# KNXTransceiverBoard_Aufsteck_V1.net
KiCad netlist of a schematic drawn in EAGLE
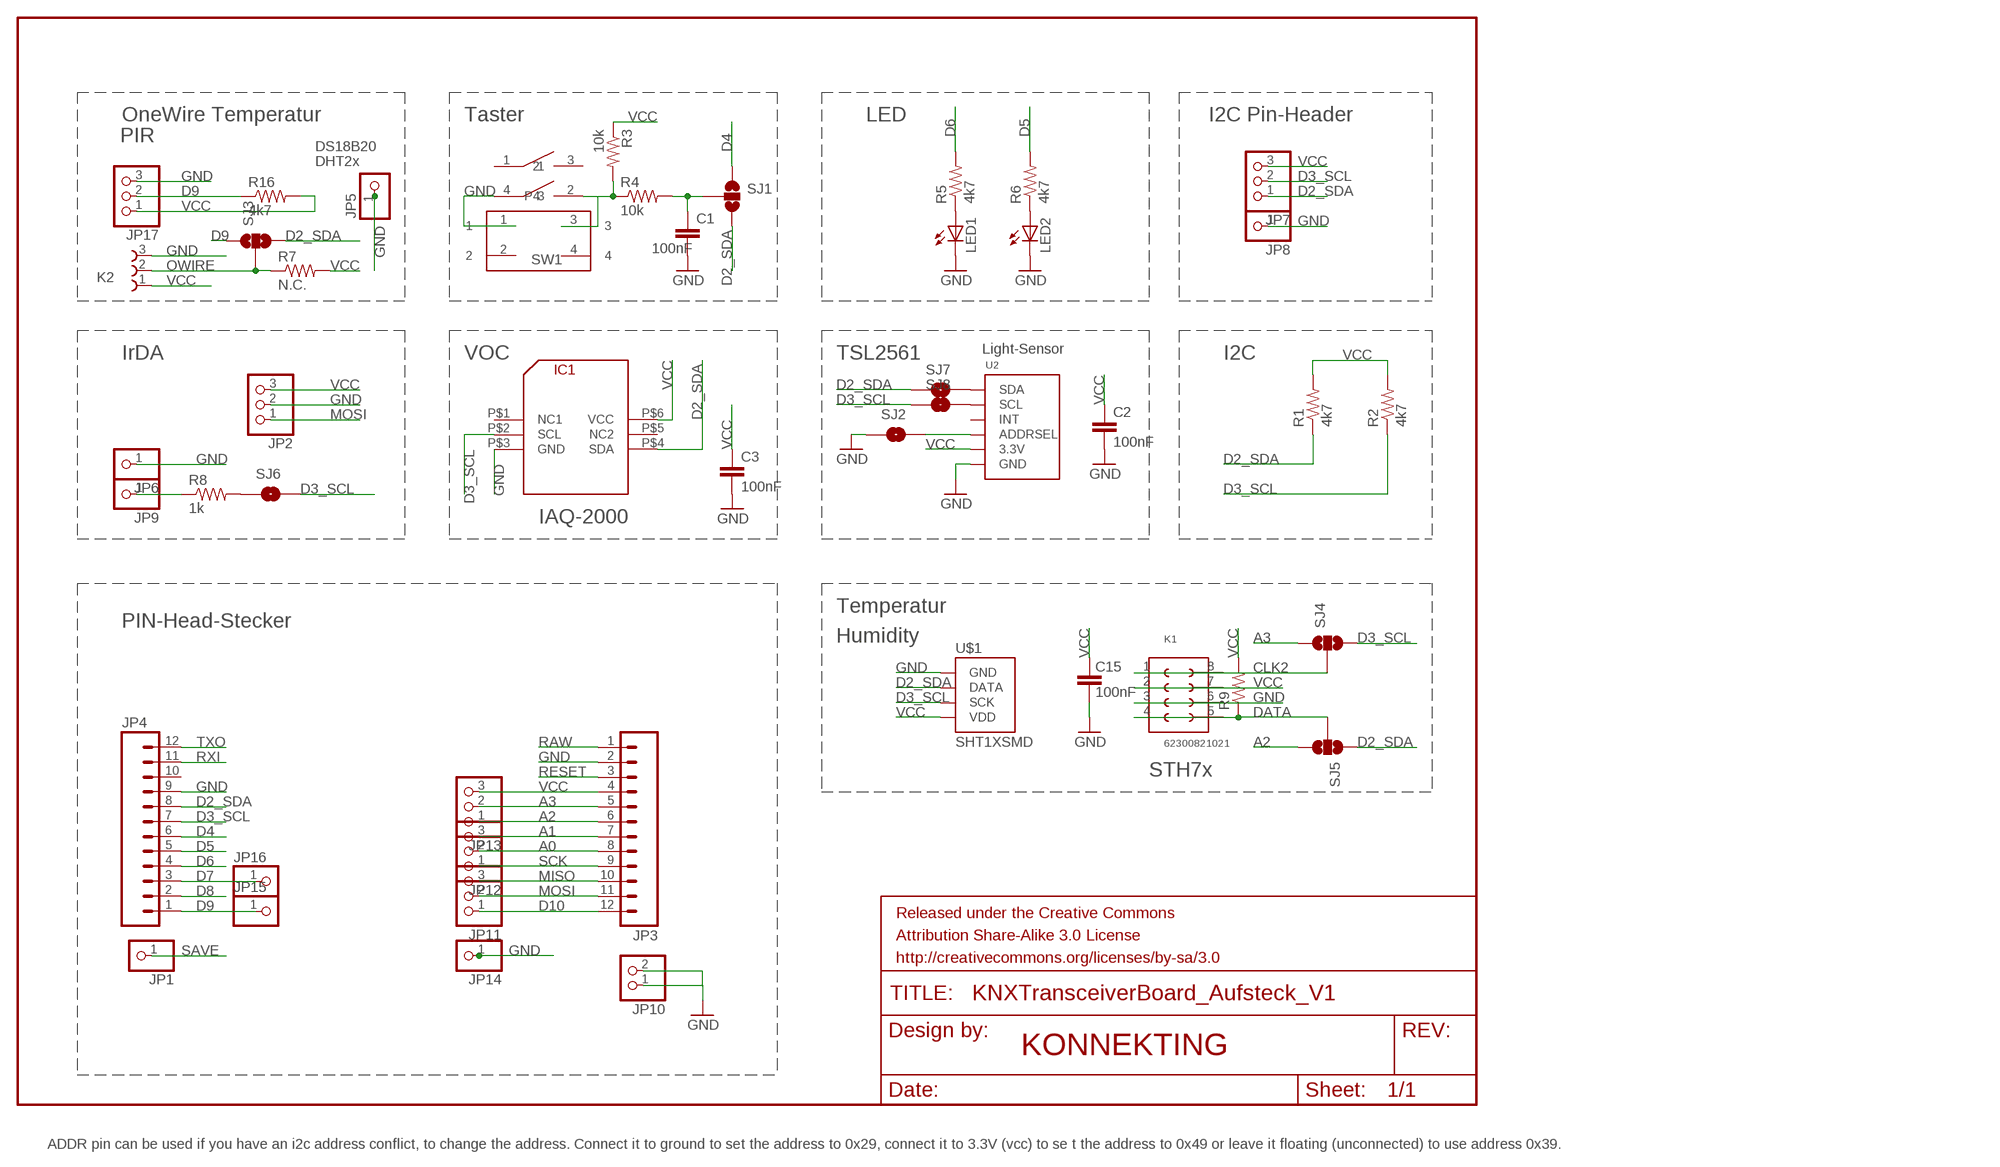
[diagram p0: schematic, sheet 1]

(export (version "E")
  (design (tool "Eeschema 10.0.6"))
  (components
    (comp (ref "C1")
      (value "100nF")
      (footprint "eagle-import:C0603")
      (libsource (lib "eagle-import") (part "C-EUC0603"))
    )
    (comp (ref "C2")
      (value "100nF")
      (footprint "eagle-import:C0603")
      (libsource (lib "eagle-import") (part "C-EUC0603"))
    )
    (comp (ref "C3")
      (value "100nF")
      (footprint "eagle-import:C0603")
      (libsource (lib "eagle-import") (part "C-EUC0603"))
    )
    (comp (ref "C15")
      (value "100nF")
      (footprint "eagle-import:0603-CAP")
      (libsource (lib "eagle-import") (part "CAP0603-CAP"))
    )
    (comp (ref "FRAME1")
      (value "FRAME-LETTER")
      (footprint "eagle-import:CREATIVE_COMMONS")
      (libsource (lib "eagle-import") (part "FRAME-LETTER"))
    )
    (comp (ref "IC1")
      (value "AMSVOC")
      (footprint "eagle-import:AMSVOC")
      (libsource (lib "eagle-import") (part "AMSVOC"))
    )
    (comp (ref "JP1")
      (value "PINHD-1X1")
      (footprint "eagle-import:1X01")
      (libsource (lib "eagle-import") (part "pinhead_PINHD-1X1"))
    )
    (comp (ref "JP2")
      (value "PINHD-1X3")
      (footprint "eagle-import:1X03")
      (libsource (lib "eagle-import") (part "PINHD-1X3"))
    )
    (comp (ref "JP3")
      (value "M12PTH")
      (footprint "eagle-import:1X12")
      (libsource (lib "eagle-import") (part "M12PTH"))
    )
    (comp (ref "JP4")
      (value "M12PTH")
      (footprint "eagle-import:1X12")
      (libsource (lib "eagle-import") (part "M12PTH"))
    )
    (comp (ref "JP5")
      (value "PINHD-1X1")
      (footprint "eagle-import:1X01")
      (libsource (lib "eagle-import") (part "pinhead_PINHD-1X1"))
    )
    (comp (ref "JP6")
      (value "PINHD-1X1")
      (footprint "eagle-import:1X01")
      (libsource (lib "eagle-import") (part "PINHD-1X1"))
    )
    (comp (ref "JP7")
      (value "PINHD-1X3")
      (footprint "eagle-import:1X03")
      (libsource (lib "eagle-import") (part "PINHD-1X3"))
    )
    (comp (ref "JP8")
      (value "PINHD-1X1")
      (footprint "eagle-import:1X01")
      (libsource (lib "eagle-import") (part "PINHD-1X1"))
    )
    (comp (ref "JP9")
      (value "PINHD-1X1")
      (footprint "eagle-import:1X01")
      (libsource (lib "eagle-import") (part "PINHD-1X1"))
    )
    (comp (ref "JP10")
      (value "PINHD-1X2")
      (footprint "eagle-import:1X02")
      (libsource (lib "eagle-import") (part "PINHD-1X2"))
    )
    (comp (ref "JP11")
      (value "PINHD-1X3")
      (footprint "eagle-import:1X03")
      (libsource (lib "eagle-import") (part "PINHD-1X3"))
    )
    (comp (ref "JP12")
      (value "PINHD-1X3")
      (footprint "eagle-import:1X03")
      (libsource (lib "eagle-import") (part "PINHD-1X3"))
    )
    (comp (ref "JP13")
      (value "PINHD-1X3")
      (footprint "eagle-import:1X03")
      (libsource (lib "eagle-import") (part "PINHD-1X3"))
    )
    (comp (ref "JP14")
      (value "PINHD-1X1")
      (footprint "eagle-import:1X01")
      (libsource (lib "eagle-import") (part "pinhead_PINHD-1X1"))
    )
    (comp (ref "JP15")
      (value "PINHD-1X1")
      (footprint "eagle-import:1X01")
      (libsource (lib "eagle-import") (part "pinhead_PINHD-1X1"))
    )
    (comp (ref "JP16")
      (value "PINHD-1X1")
      (footprint "eagle-import:1X01")
      (libsource (lib "eagle-import") (part "pinhead_PINHD-1X1"))
    )
    (comp (ref "JP17")
      (value "PINHD-1X3")
      (footprint "eagle-import:1X03")
      (libsource (lib "eagle-import") (part "PINHD-1X3"))
    )
    (comp (ref "K1")
      (value "62300821021")
      (footprint "eagle-import:62300821021")
      (libsource (lib "eagle-import") (part "62300821021"))
    )
    (comp (ref "K2")
      (value "691101710003")
      (footprint "eagle-import:691101710003")
      (libsource (lib "eagle-import") (part "691101710003"))
    )
    (comp (ref "LED1")
      (value "LEDCHIPLED_0805")
      (footprint "eagle-import:CHIPLED_0805")
      (libsource (lib "eagle-import") (part "LEDCHIPLED_0805"))
    )
    (comp (ref "LED2")
      (value "LEDCHIPLED_0805")
      (footprint "eagle-import:CHIPLED_0805")
      (libsource (lib "eagle-import") (part "LEDCHIPLED_0805"))
    )
    (comp (ref "R1")
      (value "4k7")
      (footprint "eagle-import:0603-RES")
      (libsource (lib "eagle-import") (part "RESISTOR0603-RES"))
    )
    (comp (ref "R2")
      (value "4k7")
      (footprint "eagle-import:0603-RES")
      (libsource (lib "eagle-import") (part "RESISTOR0603-RES"))
    )
    (comp (ref "R3")
      (value "10k")
      (footprint "eagle-import:0603-RES")
      (libsource (lib "eagle-import") (part "RESISTOR0603-RES"))
    )
    (comp (ref "R4")
      (value "10k")
      (footprint "eagle-import:0603-RES")
      (libsource (lib "eagle-import") (part "RESISTOR0603-RES"))
    )
    (comp (ref "R5")
      (value "4k7")
      (footprint "eagle-import:0603-RES")
      (libsource (lib "eagle-import") (part "RESISTOR0603-RES"))
    )
    (comp (ref "R6")
      (value "4k7")
      (footprint "eagle-import:0603-RES")
      (libsource (lib "eagle-import") (part "RESISTOR0603-RES"))
    )
    (comp (ref "R7")
      (value "N.C.")
      (footprint "eagle-import:0603-RES")
      (libsource (lib "eagle-import") (part "RESISTOR0603-RES"))
    )
    (comp (ref "R8")
      (value "1k")
      (footprint "eagle-import:0603-RES")
      (libsource (lib "eagle-import") (part "RESISTOR0603-RES"))
    )
    (comp (ref "R9")
      (value "RESISTOR0603-RES")
      (footprint "eagle-import:0603-RES")
      (libsource (lib "eagle-import") (part "RESISTOR0603-RES"))
    )
    (comp (ref "R16")
      (value "4k7")
      (footprint "eagle-import:0603-RES")
      (libsource (lib "eagle-import") (part "RESISTOR0603-RES"))
    )
    (comp (ref "SJ1")
      (value "SOLDERJUMPER_2WAY-OLDS")
      (footprint "eagle-import:SJ_3")
      (libsource (lib "eagle-import") (part "SOLDERJUMPER_2WAY-OLDS"))
    )
    (comp (ref "SJ2")
      (value "SOLDERJUMPERNO")
      (footprint "eagle-import:SJ_2S-NO")
      (libsource (lib "eagle-import") (part "SOLDERJUMPERNO"))
    )
    (comp (ref "SJ3")
      (value "SOLDERJUMPER_2WAY-OLDS")
      (footprint "eagle-import:SJ_3")
      (libsource (lib "eagle-import") (part "SOLDERJUMPER_2WAY-OLDS"))
    )
    (comp (ref "SJ4")
      (value "SOLDERJUMPER_2WAY-OLDS")
      (footprint "eagle-import:SJ_3")
      (libsource (lib "eagle-import") (part "SOLDERJUMPER_2WAY-OLDS"))
    )
    (comp (ref "SJ5")
      (value "SOLDERJUMPER_2WAY-OLDS")
      (footprint "eagle-import:SJ_3")
      (libsource (lib "eagle-import") (part "SOLDERJUMPER_2WAY-OLDS"))
    )
    (comp (ref "SJ6")
      (value "SOLDERJUMPERNO")
      (footprint "eagle-import:SJ_2S-NO")
      (libsource (lib "eagle-import") (part "SOLDERJUMPERNO"))
    )
    (comp (ref "SJ7")
      (value "SOLDERJUMPERNO")
      (footprint "eagle-import:SJ_2S-NO")
      (libsource (lib "eagle-import") (part "SOLDERJUMPERNO"))
    )
    (comp (ref "SJ8")
      (value "SOLDERJUMPERNO")
      (footprint "eagle-import:SJ_2S-NO")
      (libsource (lib "eagle-import") (part "SOLDERJUMPERNO"))
    )
    (comp (ref "SW1")
      (value "430156095926")
      (footprint "eagle-import:430156095926")
      (libsource (lib "eagle-import") (part "430156095926"))
    )
    (comp (ref "U$1")
      (value "SHT1XSMD")
      (footprint "eagle-import:SHT1X")
      (libsource (lib "eagle-import") (part "SHT1XSMD"))
    )
    (comp (ref "U$2")
      (value "TASTER")
      (footprint "eagle-import:TASTER")
      (libsource (lib "eagle-import") (part "TASTER"))
    )
    (comp (ref "U2")
      (value "TSL2561")
      (footprint "eagle-import:TSL2561_FN")
      (libsource (lib "eagle-import") (part "TSL2561"))
    )
  )
  (nets
    (net (code "1") (name "/A0") (class "Default")
      (node (ref "JP12") (pin "2") (pinfunction "2_2") (pintype "passive"))
      (node (ref "JP3") (pin "8") (pinfunction "8_8") (pintype "passive"))
    )
    (net (code "2") (name "/A1") (class "Default")
      (node (ref "JP12") (pin "3") (pinfunction "3_3") (pintype "passive"))
      (node (ref "JP3") (pin "7") (pinfunction "7_7") (pintype "passive"))
    )
    (net (code "3") (name "/A2") (class "Default")
      (node (ref "JP13") (pin "1") (pinfunction "1_1") (pintype "passive"))
      (node (ref "JP3") (pin "6") (pinfunction "6_6") (pintype "passive"))
      (node (ref "SJ5") (pin "3") (pinfunction "3_3") (pintype "passive"))
    )
    (net (code "4") (name "/A3") (class "Default")
      (node (ref "JP13") (pin "2") (pinfunction "2_2") (pintype "passive"))
      (node (ref "JP3") (pin "5") (pinfunction "5_5") (pintype "passive"))
      (node (ref "SJ4") (pin "1") (pinfunction "1_1") (pintype "passive"))
    )
    (net (code "5") (name "/CLK2") (class "Default")
      (node (ref "K1") (pin "1") (pinfunction "1_1") (pintype "passive"))
      (node (ref "K1") (pin "8") (pinfunction "8_8") (pintype "passive"))
      (node (ref "SJ4") (pin "2") (pinfunction "2_2") (pintype "passive"))
    )
    (net (code "6") (name "/D2_SDA") (class "Default")
      (node (ref "IC1") (pin "P$4") (pinfunction "SDA_P$4") (pintype "bidirectional"))
      (node (ref "JP4") (pin "8") (pinfunction "8_8") (pintype "passive"))
      (node (ref "JP7") (pin "1") (pinfunction "1_1") (pintype "passive"))
      (node (ref "R1") (pin "1") (pinfunction "1_1") (pintype "passive"))
      (node (ref "SJ1") (pin "3") (pinfunction "3_3") (pintype "passive"))
      (node (ref "SJ3") (pin "3") (pinfunction "3_3") (pintype "passive"))
      (node (ref "SJ5") (pin "1") (pinfunction "1_1") (pintype "passive"))
      (node (ref "SJ7") (pin "1") (pinfunction "1_1") (pintype "passive"))
      (node (ref "U$1") (pin "2") (pinfunction "DATA_2") (pintype "bidirectional"))
    )
    (net (code "7") (name "/D3_SCL") (class "Default")
      (node (ref "IC1") (pin "P$2") (pinfunction "SCL_P$2") (pintype "bidirectional"))
      (node (ref "JP4") (pin "7") (pinfunction "7_7") (pintype "passive"))
      (node (ref "JP7") (pin "2") (pinfunction "2_2") (pintype "passive"))
      (node (ref "R2") (pin "1") (pinfunction "1_1") (pintype "passive"))
      (node (ref "SJ4") (pin "3") (pinfunction "3_3") (pintype "passive"))
      (node (ref "SJ6") (pin "2") (pinfunction "2_2") (pintype "passive"))
      (node (ref "SJ8") (pin "1") (pinfunction "1_1") (pintype "passive"))
      (node (ref "U$1") (pin "3") (pinfunction "SCK_3") (pintype "input"))
    )
    (net (code "8") (name "/D4") (class "Default")
      (node (ref "JP4") (pin "6") (pinfunction "6_6") (pintype "passive"))
      (node (ref "SJ1") (pin "1") (pinfunction "1_1") (pintype "passive"))
    )
    (net (code "9") (name "/D5") (class "Default")
      (node (ref "JP4") (pin "5") (pinfunction "5_5") (pintype "passive"))
      (node (ref "R6") (pin "2") (pinfunction "2_2") (pintype "passive"))
    )
    (net (code "10") (name "/D6") (class "Default")
      (node (ref "JP4") (pin "4") (pinfunction "4_4") (pintype "passive"))
      (node (ref "R5") (pin "2") (pinfunction "2_2") (pintype "passive"))
    )
    (net (code "11") (name "/D7") (class "Default")
      (node (ref "JP16") (pin "1") (pinfunction "1_1") (pintype "passive"))
      (node (ref "JP4") (pin "3") (pinfunction "3_3") (pintype "passive"))
    )
    (net (code "12") (name "/D8") (class "Default")
      (node (ref "JP4") (pin "2") (pinfunction "2_2") (pintype "passive"))
    )
    (net (code "13") (name "/D9") (class "Default")
      (node (ref "JP15") (pin "1") (pinfunction "1_1") (pintype "passive"))
      (node (ref "JP17") (pin "2") (pinfunction "2_2") (pintype "passive"))
      (node (ref "JP4") (pin "1") (pinfunction "1_1") (pintype "passive"))
      (node (ref "R16") (pin "1") (pinfunction "1_1") (pintype "passive"))
      (node (ref "SJ3") (pin "1") (pinfunction "1_1") (pintype "passive"))
    )
    (net (code "14") (name "/D10") (class "Default")
      (node (ref "JP11") (pin "1") (pinfunction "1_1") (pintype "passive"))
      (node (ref "JP3") (pin "12") (pinfunction "12_12") (pintype "passive"))
    )
    (net (code "15") (name "/DATA") (class "Default")
      (node (ref "K1") (pin "4") (pinfunction "4_4") (pintype "passive"))
      (node (ref "K1") (pin "5") (pinfunction "5_5") (pintype "passive"))
      (node (ref "R9") (pin "1") (pinfunction "1_1") (pintype "passive"))
      (node (ref "SJ5") (pin "2") (pinfunction "2_2") (pintype "passive"))
    )
    (net (code "16") (name "/MISO") (class "Default")
      (node (ref "JP11") (pin "3") (pinfunction "3_3") (pintype "passive"))
      (node (ref "JP3") (pin "10") (pinfunction "10_10") (pintype "passive"))
    )
    (net (code "17") (name "/MOSI") (class "Default")
      (node (ref "JP11") (pin "2") (pinfunction "2_2") (pintype "passive"))
      (node (ref "JP2") (pin "1") (pinfunction "1_1") (pintype "passive"))
      (node (ref "JP3") (pin "11") (pinfunction "11_11") (pintype "passive"))
    )
    (net (code "18") (name "/OWIRE") (class "Default")
      (node (ref "K2") (pin "2") (pinfunction "2_2") (pintype "passive"))
      (node (ref "R7") (pin "1") (pinfunction "1_1") (pintype "passive"))
      (node (ref "SJ3") (pin "2") (pinfunction "2_2") (pintype "passive"))
    )
    (net (code "19") (name "/RAW") (class "Default")
      (node (ref "JP3") (pin "1") (pinfunction "1_1") (pintype "passive"))
    )
    (net (code "20") (name "/RESET") (class "Default")
      (node (ref "JP3") (pin "3") (pinfunction "3_3") (pintype "passive"))
    )
    (net (code "21") (name "/RXI") (class "Default")
      (node (ref "JP4") (pin "11") (pinfunction "11_11") (pintype "passive"))
    )
    (net (code "22") (name "/SAVE") (class "Default")
      (node (ref "JP1") (pin "1") (pinfunction "1_1") (pintype "passive"))
    )
    (net (code "23") (name "/SCK") (class "Default")
      (node (ref "JP12") (pin "1") (pinfunction "1_1") (pintype "passive"))
      (node (ref "JP3") (pin "9") (pinfunction "9_9") (pintype "passive"))
    )
    (net (code "24") (name "/TXO") (class "Default")
      (node (ref "JP4") (pin "12") (pinfunction "12_12") (pintype "passive"))
    )
    (net (code "25") (name "/VCC") (class "Default")
      (node (ref "C15") (pin "2") (pinfunction "2_2") (pintype "passive"))
      (node (ref "C2") (pin "1") (pinfunction "1_1") (pintype "passive"))
      (node (ref "C3") (pin "1") (pinfunction "1_1") (pintype "passive"))
      (node (ref "IC1") (pin "P$6") (pinfunction "VCC_P$6") (pintype "bidirectional"))
      (node (ref "JP13") (pin "3") (pinfunction "3_3") (pintype "passive"))
      (node (ref "JP17") (pin "1") (pinfunction "1_1") (pintype "passive"))
      (node (ref "JP2") (pin "3") (pinfunction "3_3") (pintype "passive"))
      (node (ref "JP3") (pin "4") (pinfunction "4_4") (pintype "passive"))
      (node (ref "JP7") (pin "3") (pinfunction "3_3") (pintype "passive"))
      (node (ref "K1") (pin "2") (pinfunction "2_2") (pintype "passive"))
      (node (ref "K1") (pin "7") (pinfunction "7_7") (pintype "passive"))
      (node (ref "K2") (pin "1") (pinfunction "1_1") (pintype "passive"))
      (node (ref "R1") (pin "2") (pinfunction "2_2") (pintype "passive"))
      (node (ref "R16") (pin "2") (pinfunction "2_2") (pintype "passive"))
      (node (ref "R2") (pin "2") (pinfunction "2_2") (pintype "passive"))
      (node (ref "R3") (pin "1") (pinfunction "1_1") (pintype "passive"))
      (node (ref "R7") (pin "2") (pinfunction "2_2") (pintype "passive"))
      (node (ref "R9") (pin "2") (pinfunction "2_2") (pintype "passive"))
      (node (ref "U$1") (pin "4") (pinfunction "VDD_4") (pintype "power_in"))
      (node (ref "U2") (pin "VDD") (pinfunction "3.3V_VDD") (pintype "bidirectional"))
    )
    (net (code "26") (name "GND") (class "Default")
      (node (ref "C1") (pin "2") (pinfunction "2_2") (pintype "passive"))
      (node (ref "C15") (pin "1") (pinfunction "1_1") (pintype "passive"))
      (node (ref "C2") (pin "2") (pinfunction "2_2") (pintype "passive"))
      (node (ref "C3") (pin "2") (pinfunction "2_2") (pintype "passive"))
      (node (ref "IC1") (pin "P$3") (pinfunction "GND_P$3") (pintype "bidirectional"))
      (node (ref "JP10") (pin "1") (pinfunction "1_1") (pintype "passive"))
      (node (ref "JP10") (pin "2") (pinfunction "2_2") (pintype "passive"))
      (node (ref "JP14") (pin "1") (pinfunction "1_1") (pintype "passive"))
      (node (ref "JP17") (pin "3") (pinfunction "3_3") (pintype "passive"))
      (node (ref "JP2") (pin "2") (pinfunction "2_2") (pintype "passive"))
      (node (ref "JP3") (pin "2") (pinfunction "2_2") (pintype "passive"))
      (node (ref "JP4") (pin "9") (pinfunction "9_9") (pintype "passive"))
      (node (ref "JP5") (pin "1") (pinfunction "1_1") (pintype "passive"))
      (node (ref "JP6") (pin "1") (pinfunction "1_1") (pintype "passive"))
      (node (ref "JP8") (pin "1") (pinfunction "1_1") (pintype "passive"))
      (node (ref "K1") (pin "3") (pinfunction "3_3") (pintype "passive"))
      (node (ref "K1") (pin "6") (pinfunction "6_6") (pintype "passive"))
      (node (ref "K2") (pin "3") (pinfunction "3_3") (pintype "passive"))
      (node (ref "LED1") (pin "C") (pinfunction "C_C") (pintype "passive"))
      (node (ref "LED2") (pin "C") (pinfunction "C_C") (pintype "passive"))
      (node (ref "SJ2") (pin "1") (pinfunction "1_1") (pintype "passive"))
      (node (ref "SW1") (pin "1") (pinfunction "1_1") (pintype "bidirectional"))
      (node (ref "U$1") (pin "1") (pinfunction "GND_1") (pintype "power_in"))
      (node (ref "U$2") (pin "4") (pinfunction "3_4") (pintype "bidirectional"))
      (node (ref "U2") (pin "VSS") (pinfunction "GND_VSS") (pintype "bidirectional"))
    )
    (net (code "27") (name "Net-(C1-Pad1)") (class "Default")
      (node (ref "C1") (pin "1") (pinfunction "1_1") (pintype "passive"))
      (node (ref "R4") (pin "2") (pinfunction "2_2") (pintype "passive"))
      (node (ref "SJ1") (pin "2") (pinfunction "2_2") (pintype "passive"))
    )
    (net (code "28") (name "Net-(JP9-Pad1)") (class "Default")
      (node (ref "JP9") (pin "1") (pinfunction "1_1") (pintype "passive"))
      (node (ref "R8") (pin "1") (pinfunction "1_1") (pintype "passive"))
    )
    (net (code "29") (name "Net-(LED1-PadA)") (class "Default")
      (node (ref "LED1") (pin "A") (pinfunction "A_A") (pintype "passive"))
      (node (ref "R5") (pin "1") (pinfunction "1_1") (pintype "passive"))
    )
    (net (code "30") (name "Net-(LED2-PadA)") (class "Default")
      (node (ref "LED2") (pin "A") (pinfunction "A_A") (pintype "passive"))
      (node (ref "R6") (pin "1") (pinfunction "1_1") (pintype "passive"))
    )
    (net (code "31") (name "Net-(R8-Pad2)") (class "Default")
      (node (ref "R8") (pin "2") (pinfunction "2_2") (pintype "passive"))
      (node (ref "SJ6") (pin "1") (pinfunction "1_1") (pintype "passive"))
    )
    (net (code "32") (name "Net-(U$2-P4)") (class "Default")
      (node (ref "R3") (pin "2") (pinfunction "2_2") (pintype "passive"))
      (node (ref "R4") (pin "1") (pinfunction "1_1") (pintype "passive"))
      (node (ref "SW1") (pin "3") (pinfunction "3_3") (pintype "bidirectional"))
      (node (ref "U$2") (pin "2") (pinfunction "P4_2") (pintype "bidirectional"))
    )
    (net (code "33") (name "Net-(U2-ADDRSEL)") (class "Default")
      (node (ref "SJ2") (pin "2") (pinfunction "2_2") (pintype "passive"))
      (node (ref "U2") (pin "ADR") (pinfunction "ADDRSEL_ADR") (pintype "bidirectional"))
    )
    (net (code "34") (name "Net-(U2-SCL)") (class "Default")
      (node (ref "SJ8") (pin "2") (pinfunction "2_2") (pintype "passive"))
      (node (ref "U2") (pin "CLK") (pinfunction "SCL_CLK") (pintype "bidirectional"))
    )
    (net (code "35") (name "Net-(U2-SDA)") (class "Default")
      (node (ref "SJ7") (pin "2") (pinfunction "2_2") (pintype "passive"))
      (node (ref "U2") (pin "DATA") (pinfunction "SDA_DATA") (pintype "bidirectional"))
    )
    (net (code "36") (name "unconnected-(IC1-NC1-PadP$1)") (class "Default")
      (node (ref "IC1") (pin "P$1") (pinfunction "NC1_P$1") (pintype "bidirectional"))
    )
    (net (code "37") (name "unconnected-(IC1-NC2-PadP$5)") (class "Default")
      (node (ref "IC1") (pin "P$5") (pinfunction "NC2_P$5") (pintype "bidirectional"))
    )
    (net (code "38") (name "unconnected-(JP4-Pad10)") (class "Default")
      (node (ref "JP4") (pin "10") (pinfunction "10_10") (pintype "passive"))
    )
    (net (code "39") (name "unconnected-(SW1-Pad2)") (class "Default")
      (node (ref "SW1") (pin "2") (pinfunction "2_2") (pintype "bidirectional"))
    )
    (net (code "40") (name "unconnected-(SW1-Pad4)") (class "Default")
      (node (ref "SW1") (pin "4") (pinfunction "4_4") (pintype "bidirectional"))
    )
    (net (code "41") (name "unconnected-(U$2-2-Pad3)") (class "Default")
      (node (ref "U$2") (pin "3") (pinfunction "2_3") (pintype "bidirectional"))
    )
    (net (code "42") (name "unconnected-(U$2-Pad1)") (class "Default")
      (node (ref "U$2") (pin "1") (pinfunction "1_1") (pintype "bidirectional"))
    )
    (net (code "43") (name "unconnected-(U2-PadINT)") (class "Default")
      (node (ref "U2") (pin "INT") (pinfunction "INT_INT") (pintype "bidirectional"))
    )
  )
)
